# USB_to_Serial_Adapter.net
KiCad netlist of a schematic drawn in Altium Designer
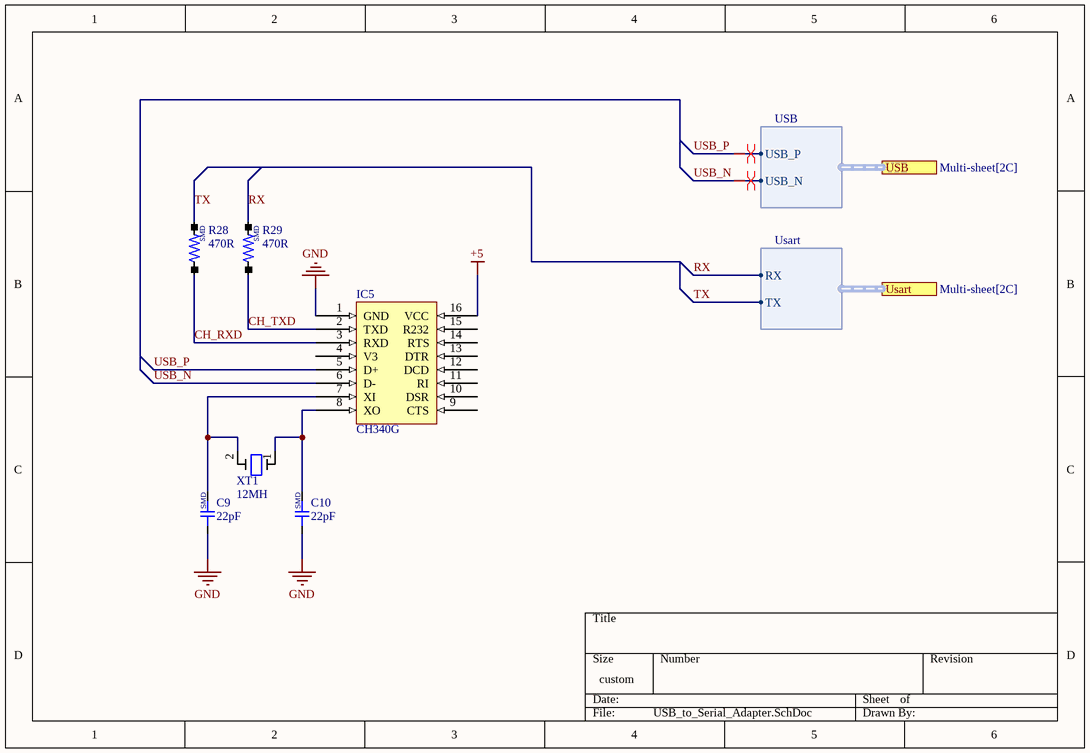
[diagram p0: USB_to_Serial_Adapter.SchDoc]

(export (version "E")
  (design (tool "Eeschema 10.0.6"))
  (components
    (comp (ref "C9") (value "22pF") (footprint "CAP-0603") (libsource (lib "kave-eng-pro") (part "cap_smd")))
    (comp (ref "C10") (value "22pF") (footprint "CAP-0603") (libsource (lib "kave-eng-pro") (part "cap_smd")))
    (comp (ref "IC5") (value "CH340G") (footprint "SOP16") (libsource (lib "kave-eng-pro") (part "ch340g")))
    (comp (ref "R28") (value "470R") (footprint "RES/0603") (libsource (lib "kave-eng-pro") (part "RES/SMD")))
    (comp (ref "R29") (value "470R") (footprint "RES/0603") (libsource (lib "kave-eng-pro") (part "RES/SMD")))
    (comp (ref "XT1") (value "12MH") (footprint "XTL16MH") (libsource (lib "kave-eng-pro") (part "XTL16")))
  )
  (nets
    (net (code "3") (name "+5") (class "Default")
      (node (ref "IC5") (pin "16") (pinfunction "VCC_16") (pintype "input"))
    )
    (net (code "4") (name "/CH_RXD") (class "Default")
      (node (ref "IC5") (pin "3") (pinfunction "RXD_3") (pintype "input"))
      (node (ref "R28") (pin "1") (pinfunction "1_1") (pintype "passive"))
    )
    (net (code "5") (name "/CH_TXD") (class "Default")
      (node (ref "IC5") (pin "2") (pinfunction "TXD_2") (pintype "input"))
      (node (ref "R29") (pin "1") (pinfunction "1_1") (pintype "passive"))
    )
    (net (code "6") (name "/RX") (class "Default")
      (node (ref "R29") (pin "2") (pinfunction "2_2") (pintype "passive"))
    )
    (net (code "7") (name "/TX") (class "Default")
      (node (ref "R28") (pin "2") (pinfunction "2_2") (pintype "passive"))
    )
    (net (code "8") (name "/USB_N") (class "Default")
      (node (ref "IC5") (pin "6") (pinfunction "D-_6") (pintype "input"))
    )
    (net (code "9") (name "/USB_P") (class "Default")
      (node (ref "IC5") (pin "5") (pinfunction "D+_5") (pintype "input"))
    )
    (net (code "12") (name "GND") (class "Default")
      (node (ref "C10") (pin "1") (pintype "passive"))
      (node (ref "C9") (pin "1") (pintype "passive"))
      (node (ref "IC5") (pin "1") (pinfunction "GND_1") (pintype "input"))
    )
    (net (code "13") (name "Net-(IC5-XI)") (class "Default")
      (node (ref "C9") (pin "2") (pintype "passive"))
      (node (ref "IC5") (pin "7") (pinfunction "XI_7") (pintype "input"))
      (node (ref "XT1") (pin "2") (pintype "passive"))
    )
    (net (code "14") (name "Net-(IC5-XO)") (class "Default")
      (node (ref "C10") (pin "2") (pintype "passive"))
      (node (ref "IC5") (pin "8") (pinfunction "XO_8") (pintype "input"))
      (node (ref "XT1") (pin "1") (pintype "passive"))
    )
    (net (code "15") (name "unconnected-(IC5-CTS-Pad9)") (class "Default")
      (node (ref "IC5") (pin "9") (pinfunction "CTS_9") (pintype "input"))
    )
    (net (code "16") (name "unconnected-(IC5-DCD-Pad12)") (class "Default")
      (node (ref "IC5") (pin "12") (pinfunction "DCD_12") (pintype "input"))
    )
    (net (code "17") (name "unconnected-(IC5-DSR-Pad10)") (class "Default")
      (node (ref "IC5") (pin "10") (pinfunction "DSR_10") (pintype "input"))
    )
    (net (code "18") (name "unconnected-(IC5-DTR-Pad13)") (class "Default")
      (node (ref "IC5") (pin "13") (pinfunction "DTR_13") (pintype "input"))
    )
    (net (code "19") (name "unconnected-(IC5-R232-Pad15)") (class "Default")
      (node (ref "IC5") (pin "15") (pinfunction "R232_15") (pintype "input"))
    )
    (net (code "20") (name "unconnected-(IC5-RI-Pad11)") (class "Default")
      (node (ref "IC5") (pin "11") (pinfunction "RI_11") (pintype "input"))
    )
    (net (code "21") (name "unconnected-(IC5-RTS-Pad14)") (class "Default")
      (node (ref "IC5") (pin "14") (pinfunction "RTS_14") (pintype "input"))
    )
    (net (code "22") (name "unconnected-(IC5-V3-Pad4)") (class "Default")
      (node (ref "IC5") (pin "4") (pinfunction "V3_4") (pintype "input"))
    )
  )
)
